# PowerSupply.net
KiCad netlist of a schematic drawn in Altium Designer
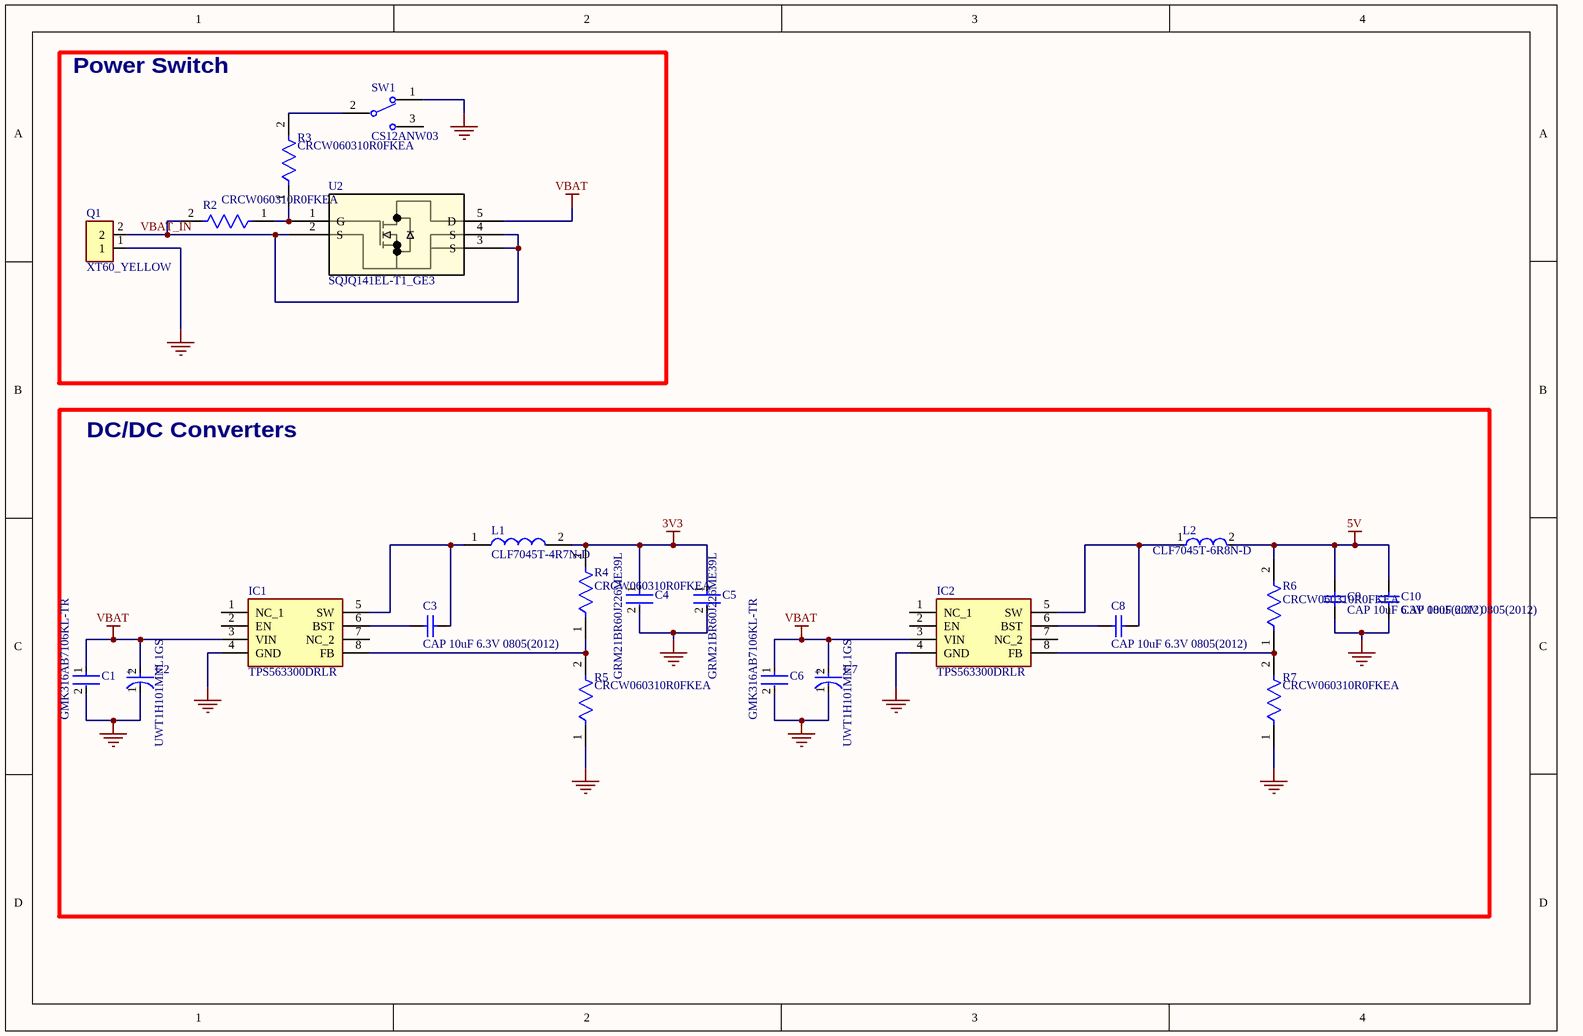
[diagram p0: PowerSupply.SchDoc]

(export (version "E")
  (design (tool "Eeschema 10.0.6"))
  (components
    (comp (ref "C1")
      (value "GMK316AB7106KL-TR")
      (footprint "FP-1206-L_3_2_0_2-W_1_6_0-IPC_C")
      (description "None")
      (fields (field (name "TOLERANCE") "10%"))
      (libsource (lib "Altium Content Vault") (part "b4654b650e69147ec39a6b967a45e02"))
    )
    (comp (ref "C2")
      (value "UWT1H101MNL1GS")
      (footprint "FP-UWT1H101MNL1GS-MFG")
      (description "CAP ALUM 100UF 20% 50V SMD")
      (fields (field (name "TOLERANCE") "20%") (field (name "VOLTAGE") "50V"))
      (libsource (lib "Altium Content Vault") (part "203bc49f2ac43e59fd269a8c329ed05"))
    )
    (comp (ref "C3")
      (value "CAP 10uF 6.3V 0805(2012)")
      (footprint "CAPC0805(2012)155_L")
      (description "CAP 10uF 6.3V ±10% 0805 (2012 Metric) Thickness 1.55mm SMD")
      (fields (field (name "TOLERANCE") "Â±10%"))
      (libsource (lib "Altium Content Vault") (part "CAP"))
    )
    (comp (ref "C4")
      (value "GRM21BR60J226ME39L")
      (footprint "FP-GRM21B-0_15-MFG")
      (description "Chip Multilayer Ceramic Capacitors for General Purpose, 0805, 22uF, X5R, 15%, 20%, 6.3V")
      (fields (field (name "VOLTAGE") "6.3V") (field (name "TOLERANCE") "20%"))
      (libsource (lib "Altium Content Vault") (part "b4654b650e69147ec39a6b967a45e02"))
    )
    (comp (ref "C5")
      (value "GRM21BR60J226ME39L")
      (footprint "FP-GRM21B-0_15-MFG")
      (description "Chip Multilayer Ceramic Capacitors for General Purpose, 0805, 22uF, X5R, 15%, 20%, 6.3V")
      (fields (field (name "VOLTAGE") "6.3V") (field (name "TOLERANCE") "20%"))
      (libsource (lib "Altium Content Vault") (part "b4654b650e69147ec39a6b967a45e02"))
    )
    (comp (ref "C6")
      (value "GMK316AB7106KL-TR")
      (footprint "FP-1206-L_3_2_0_2-W_1_6_0-IPC_C")
      (description "None")
      (fields (field (name "TOLERANCE") "10%"))
      (libsource (lib "Altium Content Vault") (part "b4654b650e69147ec39a6b967a45e02"))
    )
    (comp (ref "C7")
      (value "UWT1H101MNL1GS")
      (footprint "FP-UWT1H101MNL1GS-MFG")
      (description "CAP ALUM 100UF 20% 50V SMD")
      (fields (field (name "TOLERANCE") "20%") (field (name "VOLTAGE") "50V"))
      (libsource (lib "Altium Content Vault") (part "203bc49f2ac43e59fd269a8c329ed05"))
    )
    (comp (ref "C8")
      (value "CAP 10uF 6.3V 0805(2012)")
      (footprint "CAPC0805(2012)155_L")
      (description "CAP 10uF 6.3V ±10% 0805 (2012 Metric) Thickness 1.55mm SMD")
      (fields (field (name "TOLERANCE") "Â±10%"))
      (libsource (lib "Altium Content Vault") (part "CAP"))
    )
    (comp (ref "C9")
      (value "CAP 10uF 6.3V 0805(2012)")
      (footprint "CAPC0805(2012)155_L")
      (description "CAP 10uF 6.3V ±10% 0805 (2012 Metric) Thickness 1.55mm SMD")
      (fields (field (name "TOLERANCE") "Â±10%"))
      (libsource (lib "Altium Content Vault") (part "CAP"))
    )
    (comp (ref "C10")
      (value "CAP 10uF 6.3V 0805(2012)")
      (footprint "CAPC0805(2012)155_L")
      (description "CAP 10uF 6.3V ±10% 0805 (2012 Metric) Thickness 1.55mm SMD")
      (fields (field (name "TOLERANCE") "Â±10%"))
      (libsource (lib "Altium Content Vault") (part "CAP"))
    )
    (comp (ref "IC1")
      (value "TPS563300DRLR")
      (footprint "roboime:SOTFL50P160X60-8N")
      (description "Integrated Circuit")
      (fields (field (name "MOUSER PART NUMBER") "595-TPS563300DRLR"))
      (libsource (lib "roboime") (part "TPS563300DRLR"))
    )
    (comp (ref "IC2")
      (value "TPS563300DRLR")
      (footprint "roboime:SOTFL50P160X60-8N")
      (description "Integrated Circuit")
      (fields (field (name "MOUSER PART NUMBER") "595-TPS563300DRLR"))
      (libsource (lib "roboime") (part "TPS563300DRLR"))
    )
    (comp (ref "L1")
      (value "CLF7045T-4R7N-D")
      (footprint "roboime:CLF7045-D")
      (description "Inductor")
      (fields (field (name "MOUSER PART NUMBER") "810-CLF7045T-4R7N-D"))
      (libsource (lib "roboime") (part "CLF7045T-4R7N-D"))
    )
    (comp (ref "L2")
      (value "CLF7045T-6R8N-D")
      (footprint "FP-CLF7045-MFG")
      (description "FIXED IND 6.8UH 3A 27 MOHM SMD")
      (fields (field (name "TOLERANCE") "30%") (field (name "MANUFACTURER") "TDK"))
      (libsource (lib "Altium Content Vault") (part "725321dda6339637d4d059423bc1c3c"))
    )
    (comp (ref "Q1")
      (value "XT60_YELLOW")
      (footprint "AMASS_XT60PB-M")
      (description "Power connector; 65A; PIN: 2; Colour: yellow")
      (fields (field (name "MP") "XT60 YELLOW") (field (name "MF") "Pololu"))
      (libsource (lib "roboime") (part "XT60_YELLOW"))
    )
    (comp (ref "R2")
      (value "CRCW060310R0FKEA")
      (footprint "FP-CRCW0603-e3-IPC_A")
      (description "RES Thick Film, 10Ω, 1%, 0.1W, 100ppm/°C, 0603")
      (fields (field (name "TOLERANCE") "1%"))
      (libsource (lib "Altium Content Vault") (part "1029c3af85768c4190bb7ad29bc67b5"))
    )
    (comp (ref "R3")
      (value "CRCW060310R0FKEA")
      (footprint "FP-CRCW0603-e3-IPC_A")
      (description "RES Thick Film, 10Ω, 1%, 0.1W, 100ppm/°C, 0603")
      (fields (field (name "TOLERANCE") "1%"))
      (libsource (lib "Altium Content Vault") (part "1029c3af85768c4190bb7ad29bc67b5"))
    )
    (comp (ref "R4")
      (value "CRCW060310R0FKEA")
      (footprint "FP-CRCW0603-e3-IPC_A")
      (description "RES Thick Film, 10Ω, 1%, 0.1W, 100ppm/°C, 0603")
      (fields (field (name "TOLERANCE") "1%"))
      (libsource (lib "Altium Content Vault") (part "1029c3af85768c4190bb7ad29bc67b5"))
    )
    (comp (ref "R5")
      (value "CRCW060310R0FKEA")
      (footprint "FP-CRCW0603-e3-IPC_A")
      (description "RES Thick Film, 10Ω, 1%, 0.1W, 100ppm/°C, 0603")
      (fields (field (name "TOLERANCE") "1%"))
      (libsource (lib "Altium Content Vault") (part "1029c3af85768c4190bb7ad29bc67b5"))
    )
    (comp (ref "R6")
      (value "CRCW060310R0FKEA")
      (footprint "FP-CRCW0603-e3-IPC_A")
      (description "RES Thick Film, 10Ω, 1%, 0.1W, 100ppm/°C, 0603")
      (fields (field (name "TOLERANCE") "1%"))
      (libsource (lib "Altium Content Vault") (part "1029c3af85768c4190bb7ad29bc67b5"))
    )
    (comp (ref "R7")
      (value "CRCW060310R0FKEA")
      (footprint "FP-CRCW0603-e3-IPC_A")
      (description "RES Thick Film, 10Ω, 1%, 0.1W, 100ppm/°C, 0603")
      (fields (field (name "TOLERANCE") "1%"))
      (libsource (lib "Altium Content Vault") (part "1029c3af85768c4190bb7ad29bc67b5"))
    )
    (comp (ref "SW1")
      (value "CS12ANW03")
      (footprint "FP-CS12ANW03-MFG")
      (description "SWITCH SLIDE SPDT 3A 125V")
      (libsource (lib "Altium Content Vault") (part "12161840acc88c497b895bf2e19a5b1"))
    )
    (comp (ref "U2")
      (value "SQJQ141EL-T1_GE3")
      (footprint "PowerPAK_8x8L_BWL-2_VIS")
      (description "No Description Available")
      (fields (field (name "COPYRIGHT") "Copyright (C) 2023 Ultra Librarian. All rights reserved."))
      (libsource (lib "roboime") (part "SQJQ141EL-T1_GE3"))
    )
  )
  (nets
    (net (code "1") (name "/VBAT_IN") (class "Default")
      (node (ref "Q1") (pin "2") (pinfunction "2_2") (pintype "passive"))
      (node (ref "R2") (pin "2") (pinfunction "2_2") (pintype "passive"))
      (node (ref "U2") (pin "2") (pinfunction "S_2") (pintype "passive"))
      (node (ref "U2") (pin "3") (pinfunction "S_3") (pintype "passive"))
      (node (ref "U2") (pin "4") (pinfunction "S_4") (pintype "passive"))
    )
    (net (code "2") (name "3V3") (class "Default")
      (node (ref "C4") (pin "1") (pinfunction "1_1") (pintype "passive"))
      (node (ref "C5") (pin "1") (pinfunction "1_1") (pintype "passive"))
      (node (ref "L1") (pin "2") (pinfunction "2_2") (pintype "passive"))
      (node (ref "R4") (pin "2") (pinfunction "2_2") (pintype "passive"))
    )
    (net (code "3") (name "5V") (class "Default")
      (node (ref "C10") (pin "2") (pinfunction "2_2") (pintype "passive"))
      (node (ref "C9") (pin "2") (pinfunction "2_2") (pintype "passive"))
      (node (ref "L2") (pin "2") (pinfunction "2_2") (pintype "passive"))
      (node (ref "R6") (pin "2") (pinfunction "2_2") (pintype "passive"))
    )
    (net (code "4") (name "GND") (class "Default")
      (node (ref "C1") (pin "2") (pinfunction "2_2") (pintype "passive"))
      (node (ref "C10") (pin "1") (pinfunction "1_1") (pintype "passive"))
      (node (ref "C2") (pin "1") (pinfunction "C_1") (pintype "passive"))
      (node (ref "C4") (pin "2") (pinfunction "2_2") (pintype "passive"))
      (node (ref "C5") (pin "2") (pinfunction "2_2") (pintype "passive"))
      (node (ref "C6") (pin "2") (pinfunction "2_2") (pintype "passive"))
      (node (ref "C7") (pin "1") (pinfunction "C_1") (pintype "passive"))
      (node (ref "C9") (pin "1") (pinfunction "1_1") (pintype "passive"))
      (node (ref "IC1") (pin "4") (pinfunction "GND_4") (pintype "passive"))
      (node (ref "IC2") (pin "4") (pinfunction "GND_4") (pintype "passive"))
      (node (ref "Q1") (pin "1") (pinfunction "1_1") (pintype "passive"))
      (node (ref "R5") (pin "1") (pinfunction "1_1") (pintype "passive"))
      (node (ref "R7") (pin "1") (pinfunction "1_1") (pintype "passive"))
      (node (ref "SW1") (pin "1") (pinfunction "1_1") (pintype "passive"))
    )
    (net (code "5") (name "Net-(IC1-BST)") (class "Default")
      (node (ref "C3") (pin "2") (pinfunction "2_2") (pintype "passive"))
      (node (ref "IC1") (pin "6") (pinfunction "BST_6") (pintype "passive"))
    )
    (net (code "6") (name "Net-(IC1-FB)") (class "Default")
      (node (ref "IC1") (pin "8") (pinfunction "FB_8") (pintype "passive"))
      (node (ref "R4") (pin "1") (pinfunction "1_1") (pintype "passive"))
      (node (ref "R5") (pin "2") (pinfunction "2_2") (pintype "passive"))
    )
    (net (code "7") (name "Net-(IC1-SW)") (class "Default")
      (node (ref "C3") (pin "1") (pinfunction "1_1") (pintype "passive"))
      (node (ref "IC1") (pin "5") (pinfunction "SW_5") (pintype "passive"))
      (node (ref "L1") (pin "1") (pinfunction "1_1") (pintype "passive"))
    )
    (net (code "8") (name "Net-(IC2-BST)") (class "Default")
      (node (ref "C8") (pin "2") (pinfunction "2_2") (pintype "passive"))
      (node (ref "IC2") (pin "6") (pinfunction "BST_6") (pintype "passive"))
    )
    (net (code "9") (name "Net-(IC2-FB)") (class "Default")
      (node (ref "IC2") (pin "8") (pinfunction "FB_8") (pintype "passive"))
      (node (ref "R6") (pin "1") (pinfunction "1_1") (pintype "passive"))
      (node (ref "R7") (pin "2") (pinfunction "2_2") (pintype "passive"))
    )
    (net (code "10") (name "Net-(IC2-SW)") (class "Default")
      (node (ref "C8") (pin "1") (pinfunction "1_1") (pintype "passive"))
      (node (ref "IC2") (pin "5") (pinfunction "SW_5") (pintype "passive"))
      (node (ref "L2") (pin "1") (pinfunction "1_1") (pintype "passive"))
    )
    (net (code "11") (name "Net-(SW1-2(COM))") (class "Default")
      (node (ref "R3") (pin "2") (pinfunction "2_2") (pintype "passive"))
      (node (ref "SW1") (pin "2") (pinfunction "2(COM)_2") (pintype "passive"))
    )
    (net (code "12") (name "Net-(U2-G)") (class "Default")
      (node (ref "R2") (pin "1") (pinfunction "1_1") (pintype "passive"))
      (node (ref "R3") (pin "1") (pinfunction "1_1") (pintype "passive"))
      (node (ref "U2") (pin "1") (pinfunction "G_1") (pintype "passive"))
    )
    (net (code "13") (name "VBAT") (class "Default")
      (node (ref "C1") (pin "1") (pinfunction "1_1") (pintype "passive"))
      (node (ref "C2") (pin "2") (pinfunction "A_2") (pintype "passive"))
      (node (ref "C6") (pin "1") (pinfunction "1_1") (pintype "passive"))
      (node (ref "C7") (pin "2") (pinfunction "A_2") (pintype "passive"))
      (node (ref "IC1") (pin "3") (pinfunction "VIN_3") (pintype "passive"))
      (node (ref "IC2") (pin "3") (pinfunction "VIN_3") (pintype "passive"))
      (node (ref "U2") (pin "5") (pinfunction "D_5") (pintype "passive"))
    )
    (net (code "14") (name "unconnected-(IC1-EN-Pad2)") (class "Default")
      (node (ref "IC1") (pin "2") (pinfunction "EN_2") (pintype "passive"))
    )
    (net (code "15") (name "unconnected-(IC1-NC_1-Pad1)") (class "Default")
      (node (ref "IC1") (pin "1") (pinfunction "NC_1_1") (pintype "passive"))
    )
    (net (code "16") (name "unconnected-(IC1-NC_2-Pad7)") (class "Default")
      (node (ref "IC1") (pin "7") (pinfunction "NC_2_7") (pintype "passive"))
    )
    (net (code "17") (name "unconnected-(IC2-EN-Pad2)") (class "Default")
      (node (ref "IC2") (pin "2") (pinfunction "EN_2") (pintype "passive"))
    )
    (net (code "18") (name "unconnected-(IC2-NC_1-Pad1)") (class "Default")
      (node (ref "IC2") (pin "1") (pinfunction "NC_1_1") (pintype "passive"))
    )
    (net (code "19") (name "unconnected-(IC2-NC_2-Pad7)") (class "Default")
      (node (ref "IC2") (pin "7") (pinfunction "NC_2_7") (pintype "passive"))
    )
    (net (code "20") (name "unconnected-(SW1-Pad3)") (class "Default")
      (node (ref "SW1") (pin "3") (pinfunction "3_3") (pintype "passive"))
    )
  )
)
